# untitled.net
KiCad netlist of a schematic drawn in EAGLE
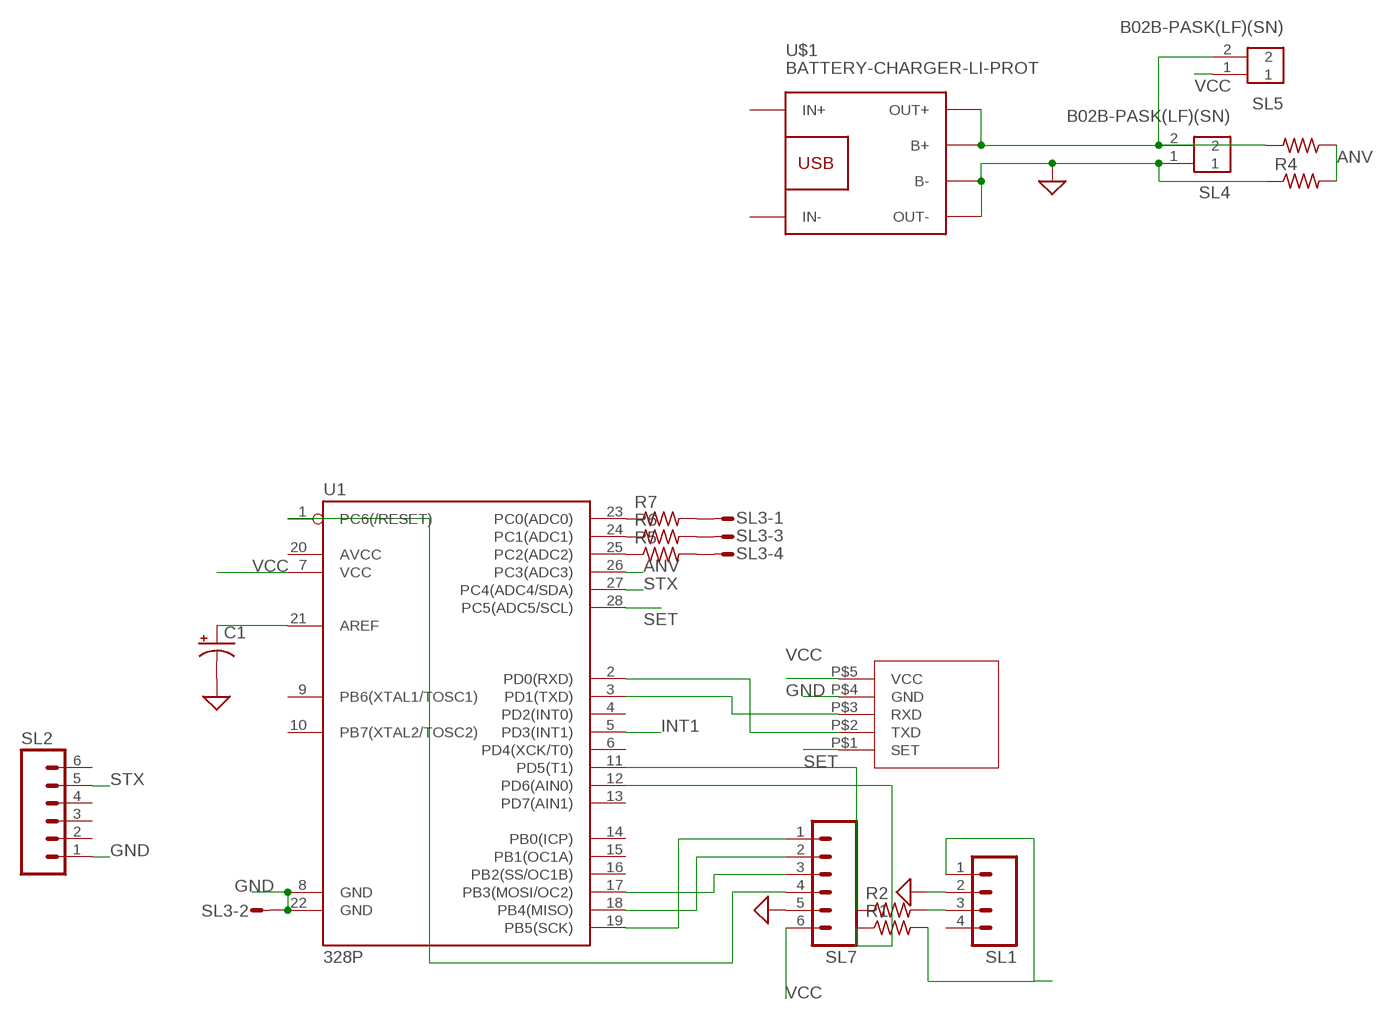
[diagram p0: schematic, sheet 1]

(export (version "E")
  (design (tool "Eeschema 10.0.6"))
  (components
    (comp (ref "C1")
      (value "CAPACITOR-PE2.5-5")
      (footprint "eagle-import:E2,5-5")
      (libsource (lib "eagle-import") (part "CAPACITOR-PE2.5-5"))
    )
    (comp (ref "R1")
      (value "R-US_0309/10")
      (footprint "eagle-import:0309_10")
      (libsource (lib "eagle-import") (part "R-US_0309/10"))
    )
    (comp (ref "R2")
      (value "R-US_0309/10")
      (footprint "eagle-import:0309_10")
      (libsource (lib "eagle-import") (part "R-US_0309/10"))
    )
    (comp (ref "R4")
      (value "R-US_0207/7")
      (footprint "eagle-import:0207_7")
      (libsource (lib "eagle-import") (part "R-US_0207/7"))
    )
    (comp (ref "R5")
      (value "R-US_0204/2V")
      (footprint "eagle-import:0204V")
      (libsource (lib "eagle-import") (part "R-US_0204/2V"))
    )
    (comp (ref "R6")
      (value "R-US_0204/2V")
      (footprint "eagle-import:0204V")
      (libsource (lib "eagle-import") (part "R-US_0204/2V"))
    )
    (comp (ref "R7")
      (value "R-US_0207/5V")
      (footprint "eagle-import:0207_5V")
      (libsource (lib "eagle-import") (part "R-US_0207/5V"))
    )
    (comp (ref "R8")
      (value "R-US_0207/7")
      (footprint "eagle-import:0207_7")
      (libsource (lib "eagle-import") (part "R-US_0207/7"))
    )
    (comp (ref "SL1")
      (value "M04")
      (footprint "eagle-import:04P")
      (libsource (lib "eagle-import") (part "M04"))
    )
    (comp (ref "SL2")
      (value "M06")
      (footprint "eagle-import:06P")
      (libsource (lib "eagle-import") (part "M06"))
    )
    (comp (ref "SL3")
      (value "M04S")
      (footprint "eagle-import:04P")
      (libsource (lib "eagle-import") (part "M04S"))
    )
    (comp (ref "SL4")
      (value "B02B-PASK(LF)(SN)")
      (footprint "eagle-import:B02B-PASK(LF)(SN)")
      (fields
        (field (name "DIGIKEY_PARTNO") "455-1817-ND")
        (field (name "MANUFACTURER") "JST Sales America Inc.")
        (field (name "CREATED_BY") "PCBLayout.com")
      )
      (libsource (lib "eagle-import") (part "B02B-PASK(LF)(SN)"))
    )
    (comp (ref "SL5")
      (value "B02B-PASK(LF)(SN)")
      (footprint "eagle-import:B02B-PASK(LF)(SN)")
      (fields
        (field (name "DIGIKEY_PARTNO") "455-1817-ND")
        (field (name "MANUFACTURER") "JST Sales America Inc.")
        (field (name "CREATED_BY") "PCBLayout.com")
      )
      (libsource (lib "eagle-import") (part "B02B-PASK(LF)(SN)"))
    )
    (comp (ref "SL7")
      (value "M06")
      (footprint "eagle-import:06P")
      (libsource (lib "eagle-import") (part "M06"))
    )
    (comp (ref "U$1")
      (value "BATTERY-CHARGER-LI-PROT")
      (footprint "eagle-import:BATTERY-CHARGER-LI-PROT")
      (libsource (lib "eagle-import") (part "BATTERY-CHARGER-LI-PROT"))
    )
    (comp (ref "U$3")
      (value "HC12")
      (footprint "eagle-import:HC12")
      (libsource (lib "eagle-import") (part "HC12"))
    )
    (comp (ref "U1")
      (value "328P")
      (footprint "eagle-import:DIP28")
      (libsource (lib "eagle-import") (part "ATMEGA328P_PDIP"))
    )
  )
  (nets
    (net (code "1") (name "/ANV") (class "Default")
      (node (ref "R4") (pin "2") (pinfunction "2_2") (pintype "passive"))
      (node (ref "R8") (pin "1") (pinfunction "1_1") (pintype "passive"))
      (node (ref "U1") (pin "26") (pinfunction "PC3(ADC3)_26") (pintype "bidirectional"))
    )
    (net (code "2") (name "/INT1") (class "Default")
      (node (ref "U1") (pin "5") (pinfunction "PD3(INT1)_5") (pintype "bidirectional"))
    )
    (net (code "3") (name "/SET") (class "Default")
      (node (ref "U$3") (pin "P$1") (pinfunction "SET_P$1") (pintype "bidirectional"))
      (node (ref "U1") (pin "28") (pinfunction "PC5(ADC5/SCL)_28") (pintype "bidirectional"))
    )
    (net (code "4") (name "/STX") (class "Default")
      (node (ref "SL2") (pin "5") (pinfunction "5_5") (pintype "passive"))
      (node (ref "U1") (pin "27") (pinfunction "PC4(ADC4/SDA)_27") (pintype "bidirectional"))
    )
    (net (code "5") (name "/VCC") (class "Default")
      (node (ref "SL5") (pin "1") (pinfunction "1_1") (pintype "passive"))
      (node (ref "SL7") (pin "6") (pinfunction "6_6") (pintype "passive"))
      (node (ref "U$3") (pin "P$5") (pinfunction "VCC_P$5") (pintype "bidirectional"))
      (node (ref "U1") (pin "7") (pinfunction "VCC_7") (pintype "bidirectional"))
    )
    (net (code "6") (name "Net-(R1-Pad2)") (class "Default")
      (node (ref "R1") (pin "2") (pinfunction "2_2") (pintype "passive"))
      (node (ref "SL1") (pin "1") (pinfunction "1_1") (pintype "passive"))
    )
    (net (code "7") (name "Net-(R2-Pad2)") (class "Default")
      (node (ref "R2") (pin "2") (pinfunction "2_2") (pintype "passive"))
      (node (ref "SL1") (pin "3") (pinfunction "3_3") (pintype "passive"))
    )
    (net (code "8") (name "Net-(R8-Pad2)") (class "Default")
      (node (ref "R8") (pin "2") (pinfunction "2_2") (pintype "passive"))
      (node (ref "SL4") (pin "2") (pinfunction "2_2") (pintype "passive"))
      (node (ref "SL5") (pin "2") (pinfunction "2_2") (pintype "passive"))
      (node (ref "U$1") (pin "B+") (pinfunction "B+_B+") (pintype "bidirectional"))
      (node (ref "U$1") (pin "OUT+") (pinfunction "OUT+_OUT+") (pintype "bidirectional"))
    )
    (net (code "9") (name "Net-(SL3A-S)") (class "Default")
      (node (ref "R7") (pin "2") (pinfunction "2_2") (pintype "passive"))
      (node (ref "SL3") (pin "1") (pinfunction "S_1") (pintype "passive"))
    )
    (net (code "10") (name "Net-(SL3C-S)") (class "Default")
      (node (ref "R6") (pin "2") (pinfunction "2_2") (pintype "passive"))
      (node (ref "SL3") (pin "3") (pinfunction "S_3") (pintype "passive"))
    )
    (net (code "11") (name "Net-(SL3D-S)") (class "Default")
      (node (ref "R5") (pin "2") (pinfunction "2_2") (pintype "passive"))
      (node (ref "SL3") (pin "4") (pinfunction "S_4") (pintype "passive"))
    )
    (net (code "12") (name "Net-(U$3-RXD)") (class "Default")
      (node (ref "U$3") (pin "P$3") (pinfunction "RXD_P$3") (pintype "bidirectional"))
      (node (ref "U1") (pin "3") (pinfunction "PD1(TXD)_3") (pintype "bidirectional"))
    )
    (net (code "13") (name "Net-(U$3-TXD)") (class "Default")
      (node (ref "U$3") (pin "P$2") (pinfunction "TXD_P$2") (pintype "bidirectional"))
      (node (ref "U1") (pin "2") (pinfunction "PD0(RXD)_2") (pintype "bidirectional"))
    )
    (net (code "14") (name "Net-(U1-AREF)") (class "Default")
      (node (ref "C1") (pin "+") (pinfunction "+_+") (pintype "passive"))
      (node (ref "U1") (pin "21") (pinfunction "AREF_21") (pintype "bidirectional"))
    )
    (net (code "15") (name "Net-(U1-PB3(MOSI{slash}OC2))") (class "Default")
      (node (ref "SL7") (pin "3") (pinfunction "3_3") (pintype "passive"))
      (node (ref "U1") (pin "17") (pinfunction "PB3(MOSI/OC2)_17") (pintype "bidirectional"))
    )
    (net (code "16") (name "Net-(U1-PB4(MISO))") (class "Default")
      (node (ref "SL7") (pin "2") (pinfunction "2_2") (pintype "passive"))
      (node (ref "U1") (pin "18") (pinfunction "PB4(MISO)_18") (pintype "bidirectional"))
    )
    (net (code "17") (name "Net-(U1-PB5(SCK))") (class "Default")
      (node (ref "SL7") (pin "1") (pinfunction "1_1") (pintype "passive"))
      (node (ref "U1") (pin "19") (pinfunction "PB5(SCK)_19") (pintype "bidirectional"))
    )
    (net (code "18") (name "Net-(U1-PC0(ADC0))") (class "Default")
      (node (ref "R7") (pin "1") (pinfunction "1_1") (pintype "passive"))
      (node (ref "U1") (pin "23") (pinfunction "PC0(ADC0)_23") (pintype "bidirectional"))
    )
    (net (code "19") (name "Net-(U1-PC1(ADC1))") (class "Default")
      (node (ref "R6") (pin "1") (pinfunction "1_1") (pintype "passive"))
      (node (ref "U1") (pin "24") (pinfunction "PC1(ADC1)_24") (pintype "bidirectional"))
    )
    (net (code "20") (name "Net-(U1-PC2(ADC2))") (class "Default")
      (node (ref "R5") (pin "1") (pinfunction "1_1") (pintype "passive"))
      (node (ref "U1") (pin "25") (pinfunction "PC2(ADC2)_25") (pintype "bidirectional"))
    )
    (net (code "21") (name "Net-(U1-PC6({slash}RESET))") (class "Default")
      (node (ref "SL7") (pin "4") (pinfunction "4_4") (pintype "passive"))
      (node (ref "U1") (pin "1") (pinfunction "PC6(/RESET)_1") (pintype "bidirectional"))
    )
    (net (code "22") (name "Net-(U1-PD5(T1))") (class "Default")
      (node (ref "R2") (pin "1") (pinfunction "1_1") (pintype "passive"))
      (node (ref "U1") (pin "11") (pinfunction "PD5(T1)_11") (pintype "bidirectional"))
    )
    (net (code "23") (name "Net-(U1-PD6(AIN0))") (class "Default")
      (node (ref "R1") (pin "1") (pinfunction "1_1") (pintype "passive"))
      (node (ref "U1") (pin "12") (pinfunction "PD6(AIN0)_12") (pintype "bidirectional"))
    )
    (net (code "24") (name "SUP") (class "Default")
      (node (ref "C1") (pin "-") (pinfunction "-_-") (pintype "passive"))
      (node (ref "R4") (pin "1") (pinfunction "1_1") (pintype "passive"))
      (node (ref "SL1") (pin "2") (pinfunction "2_2") (pintype "passive"))
      (node (ref "SL2") (pin "1") (pinfunction "1_1") (pintype "passive"))
      (node (ref "SL3") (pin "2") (pinfunction "S_2") (pintype "passive"))
      (node (ref "SL4") (pin "1") (pinfunction "1_1") (pintype "passive"))
      (node (ref "SL7") (pin "5") (pinfunction "5_5") (pintype "passive"))
      (node (ref "U$1") (pin "B-") (pinfunction "B-_B-") (pintype "bidirectional"))
      (node (ref "U$1") (pin "OUT-") (pinfunction "OUT-_OUT-") (pintype "bidirectional"))
      (node (ref "U$3") (pin "P$4") (pinfunction "GND_P$4") (pintype "bidirectional"))
      (node (ref "U1") (pin "22") (pinfunction "GND_22") (pintype "bidirectional"))
      (node (ref "U1") (pin "8") (pinfunction "GND_8") (pintype "bidirectional"))
    )
    (net (code "25") (name "unconnected-(SL1-Pad4)") (class "Default")
      (node (ref "SL1") (pin "4") (pinfunction "4_4") (pintype "passive"))
    )
    (net (code "26") (name "unconnected-(SL2-Pad2)") (class "Default")
      (node (ref "SL2") (pin "2") (pinfunction "2_2") (pintype "passive"))
    )
    (net (code "27") (name "unconnected-(SL2-Pad3)") (class "Default")
      (node (ref "SL2") (pin "3") (pinfunction "3_3") (pintype "passive"))
    )
    (net (code "28") (name "unconnected-(SL2-Pad4)") (class "Default")
      (node (ref "SL2") (pin "4") (pinfunction "4_4") (pintype "passive"))
    )
    (net (code "29") (name "unconnected-(SL2-Pad6)") (class "Default")
      (node (ref "SL2") (pin "6") (pinfunction "6_6") (pintype "passive"))
    )
    (net (code "30") (name "unconnected-(U$1-PadIN+)") (class "Default")
      (node (ref "U$1") (pin "IN+") (pinfunction "IN+_IN+") (pintype "bidirectional"))
    )
    (net (code "31") (name "unconnected-(U$1-PadIN-)") (class "Default")
      (node (ref "U$1") (pin "IN-") (pinfunction "IN-_IN-") (pintype "bidirectional"))
    )
    (net (code "32") (name "unconnected-(U1-AVCC-Pad20)") (class "Default")
      (node (ref "U1") (pin "20") (pinfunction "AVCC_20") (pintype "bidirectional"))
    )
    (net (code "33") (name "unconnected-(U1-PB0(ICP)-Pad14)") (class "Default")
      (node (ref "U1") (pin "14") (pinfunction "PB0(ICP)_14") (pintype "bidirectional"))
    )
    (net (code "34") (name "unconnected-(U1-PB1(OC1A)-Pad15)") (class "Default")
      (node (ref "U1") (pin "15") (pinfunction "PB1(OC1A)_15") (pintype "bidirectional"))
    )
    (net (code "35") (name "unconnected-(U1-PB2(SS{slash}OC1B)-Pad16)") (class "Default")
      (node (ref "U1") (pin "16") (pinfunction "PB2(SS/OC1B)_16") (pintype "bidirectional"))
    )
    (net (code "36") (name "unconnected-(U1-PB6(XTAL1{slash}TOSC1)-Pad9)") (class "Default")
      (node (ref "U1") (pin "9") (pinfunction "PB6(XTAL1/TOSC1)_9") (pintype "bidirectional"))
    )
    (net (code "37") (name "unconnected-(U1-PB7(XTAL2{slash}TOSC2)-Pad10)") (class "Default")
      (node (ref "U1") (pin "10") (pinfunction "PB7(XTAL2/TOSC2)_10") (pintype "bidirectional"))
    )
    (net (code "38") (name "unconnected-(U1-PD2(INT0)-Pad4)") (class "Default")
      (node (ref "U1") (pin "4") (pinfunction "PD2(INT0)_4") (pintype "bidirectional"))
    )
    (net (code "39") (name "unconnected-(U1-PD4(XCK{slash}T0)-Pad6)") (class "Default")
      (node (ref "U1") (pin "6") (pinfunction "PD4(XCK/T0)_6") (pintype "bidirectional"))
    )
    (net (code "40") (name "unconnected-(U1-PD7(AIN1)-Pad13)") (class "Default")
      (node (ref "U1") (pin "13") (pinfunction "PD7(AIN1)_13") (pintype "bidirectional"))
    )
  )
)
